# Sheet1.net
KiCad netlist of a schematic drawn in Altium Designer
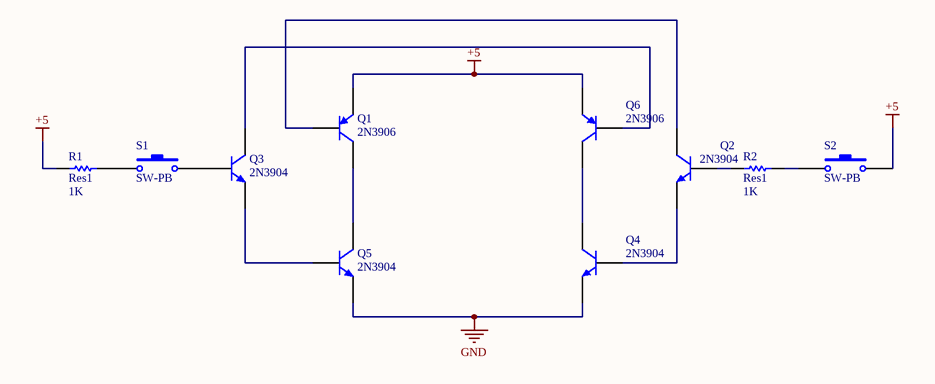
[diagram p0: Sheet1.SchDoc]

(export (version "E")
  (design (tool "Eeschema 10.0.6"))
  (components
    (comp (ref "Q1")
      (value "2N3906")
      (footprint "TO-92A")
      (description "PNP General Purpose Amplifier")
      (fields (field (name "PUBLISHER") "Altium Limited"))
      (libsource (lib "Miscellaneous Devices") (part "2N3906"))
    )
    (comp (ref "Q2")
      (value "2N3904")
      (footprint "TO-92A")
      (description "NPN General Purpose Amplifier")
      (fields (field (name "PUBLISHER") "Altium Limited"))
      (libsource (lib "Miscellaneous Devices") (part "2N3904"))
    )
    (comp (ref "Q3")
      (value "2N3904")
      (footprint "TO-92A")
      (description "NPN General Purpose Amplifier")
      (fields (field (name "PUBLISHER") "Altium Limited"))
      (libsource (lib "Miscellaneous Devices") (part "2N3904"))
    )
    (comp (ref "Q4")
      (value "2N3904")
      (footprint "TO-92A")
      (description "NPN General Purpose Amplifier")
      (fields (field (name "PUBLISHER") "Altium Limited"))
      (libsource (lib "Miscellaneous Devices") (part "2N3904"))
    )
    (comp (ref "Q5")
      (value "2N3904")
      (footprint "TO-92A")
      (description "NPN General Purpose Amplifier")
      (fields (field (name "PUBLISHER") "Altium Limited"))
      (libsource (lib "Miscellaneous Devices") (part "2N3904"))
    )
    (comp (ref "Q6")
      (value "2N3906")
      (footprint "TO-92A")
      (description "PNP General Purpose Amplifier")
      (fields (field (name "PUBLISHER") "Altium Limited"))
      (libsource (lib "Miscellaneous Devices") (part "2N3906"))
    )
    (comp (ref "R1")
      (value "Res1")
      (footprint "AXIAL-0.3")
      (description "Resistor")
      (fields (field (name "ALTIUM_VALUE") "1K") (field (name "PUBLISHER") "Altium Limited"))
      (libsource (lib "Miscellaneous Devices") (part "Res1"))
    )
    (comp (ref "R2")
      (value "Res1")
      (footprint "AXIAL-0.3")
      (description "Resistor")
      (fields (field (name "ALTIUM_VALUE") "1K") (field (name "PUBLISHER") "Altium Limited"))
      (libsource (lib "Miscellaneous Devices") (part "Res1"))
    )
    (comp (ref "S1")
      (value "SW-PB")
      (footprint "SPST-2")
      (description "Switch")
      (fields (field (name "PUBLISHER") "Altium Limited"))
      (libsource (lib "Miscellaneous Devices") (part "SW-PB"))
    )
    (comp (ref "S2")
      (value "SW-PB")
      (footprint "SPST-2")
      (description "Switch")
      (fields (field (name "PUBLISHER") "Altium Limited"))
      (libsource (lib "Miscellaneous Devices") (part "SW-PB"))
    )
  )
  (nets
    (net (code "1") (name "+5") (class "Default")
      (node (ref "Q1") (pin "1") (pinfunction "E_1") (pintype "passive"))
      (node (ref "Q6") (pin "1") (pinfunction "E_1") (pintype "passive"))
      (node (ref "R1") (pin "1") (pinfunction "1_1") (pintype "passive"))
      (node (ref "S2") (pin "2") (pinfunction "2_2") (pintype "passive"))
    )
    (net (code "2") (name "GND") (class "Default")
      (node (ref "Q4") (pin "1") (pinfunction "E_1") (pintype "passive"))
      (node (ref "Q5") (pin "1") (pinfunction "E_1") (pintype "passive"))
    )
    (net (code "3") (name "Net-(Q1-B)") (class "Default")
      (node (ref "Q1") (pin "2") (pinfunction "B_2") (pintype "passive"))
      (node (ref "Q2") (pin "3") (pinfunction "C_3") (pintype "passive"))
    )
    (net (code "4") (name "Net-(Q1-C)") (class "Default")
      (node (ref "Q1") (pin "3") (pinfunction "C_3") (pintype "passive"))
      (node (ref "Q5") (pin "3") (pinfunction "C_3") (pintype "passive"))
    )
    (net (code "5") (name "Net-(Q2-B)") (class "Default")
      (node (ref "Q2") (pin "2") (pinfunction "B_2") (pintype "passive"))
      (node (ref "R2") (pin "1") (pinfunction "1_1") (pintype "passive"))
    )
    (net (code "6") (name "Net-(Q2-E)") (class "Default")
      (node (ref "Q2") (pin "1") (pinfunction "E_1") (pintype "passive"))
      (node (ref "Q4") (pin "2") (pinfunction "B_2") (pintype "passive"))
    )
    (net (code "7") (name "Net-(Q3-B)") (class "Default")
      (node (ref "Q3") (pin "2") (pinfunction "B_2") (pintype "passive"))
      (node (ref "S1") (pin "2") (pinfunction "2_2") (pintype "passive"))
    )
    (net (code "8") (name "Net-(Q3-C)") (class "Default")
      (node (ref "Q3") (pin "3") (pinfunction "C_3") (pintype "passive"))
      (node (ref "Q6") (pin "2") (pinfunction "B_2") (pintype "passive"))
    )
    (net (code "9") (name "Net-(Q3-E)") (class "Default")
      (node (ref "Q3") (pin "1") (pinfunction "E_1") (pintype "passive"))
      (node (ref "Q5") (pin "2") (pinfunction "B_2") (pintype "passive"))
    )
    (net (code "10") (name "Net-(Q4-C)") (class "Default")
      (node (ref "Q4") (pin "3") (pinfunction "C_3") (pintype "passive"))
      (node (ref "Q6") (pin "3") (pinfunction "C_3") (pintype "passive"))
    )
    (net (code "11") (name "Net-(R1-Pad2)") (class "Default")
      (node (ref "R1") (pin "2") (pinfunction "2_2") (pintype "passive"))
      (node (ref "S1") (pin "1") (pinfunction "1_1") (pintype "passive"))
    )
    (net (code "12") (name "Net-(R2-Pad2)") (class "Default")
      (node (ref "R2") (pin "2") (pinfunction "2_2") (pintype "passive"))
      (node (ref "S2") (pin "1") (pinfunction "1_1") (pintype "passive"))
    )
  )
)
